# 2024-8-17-.net
KiCad netlist of a schematic drawn in EasyEDA Pro
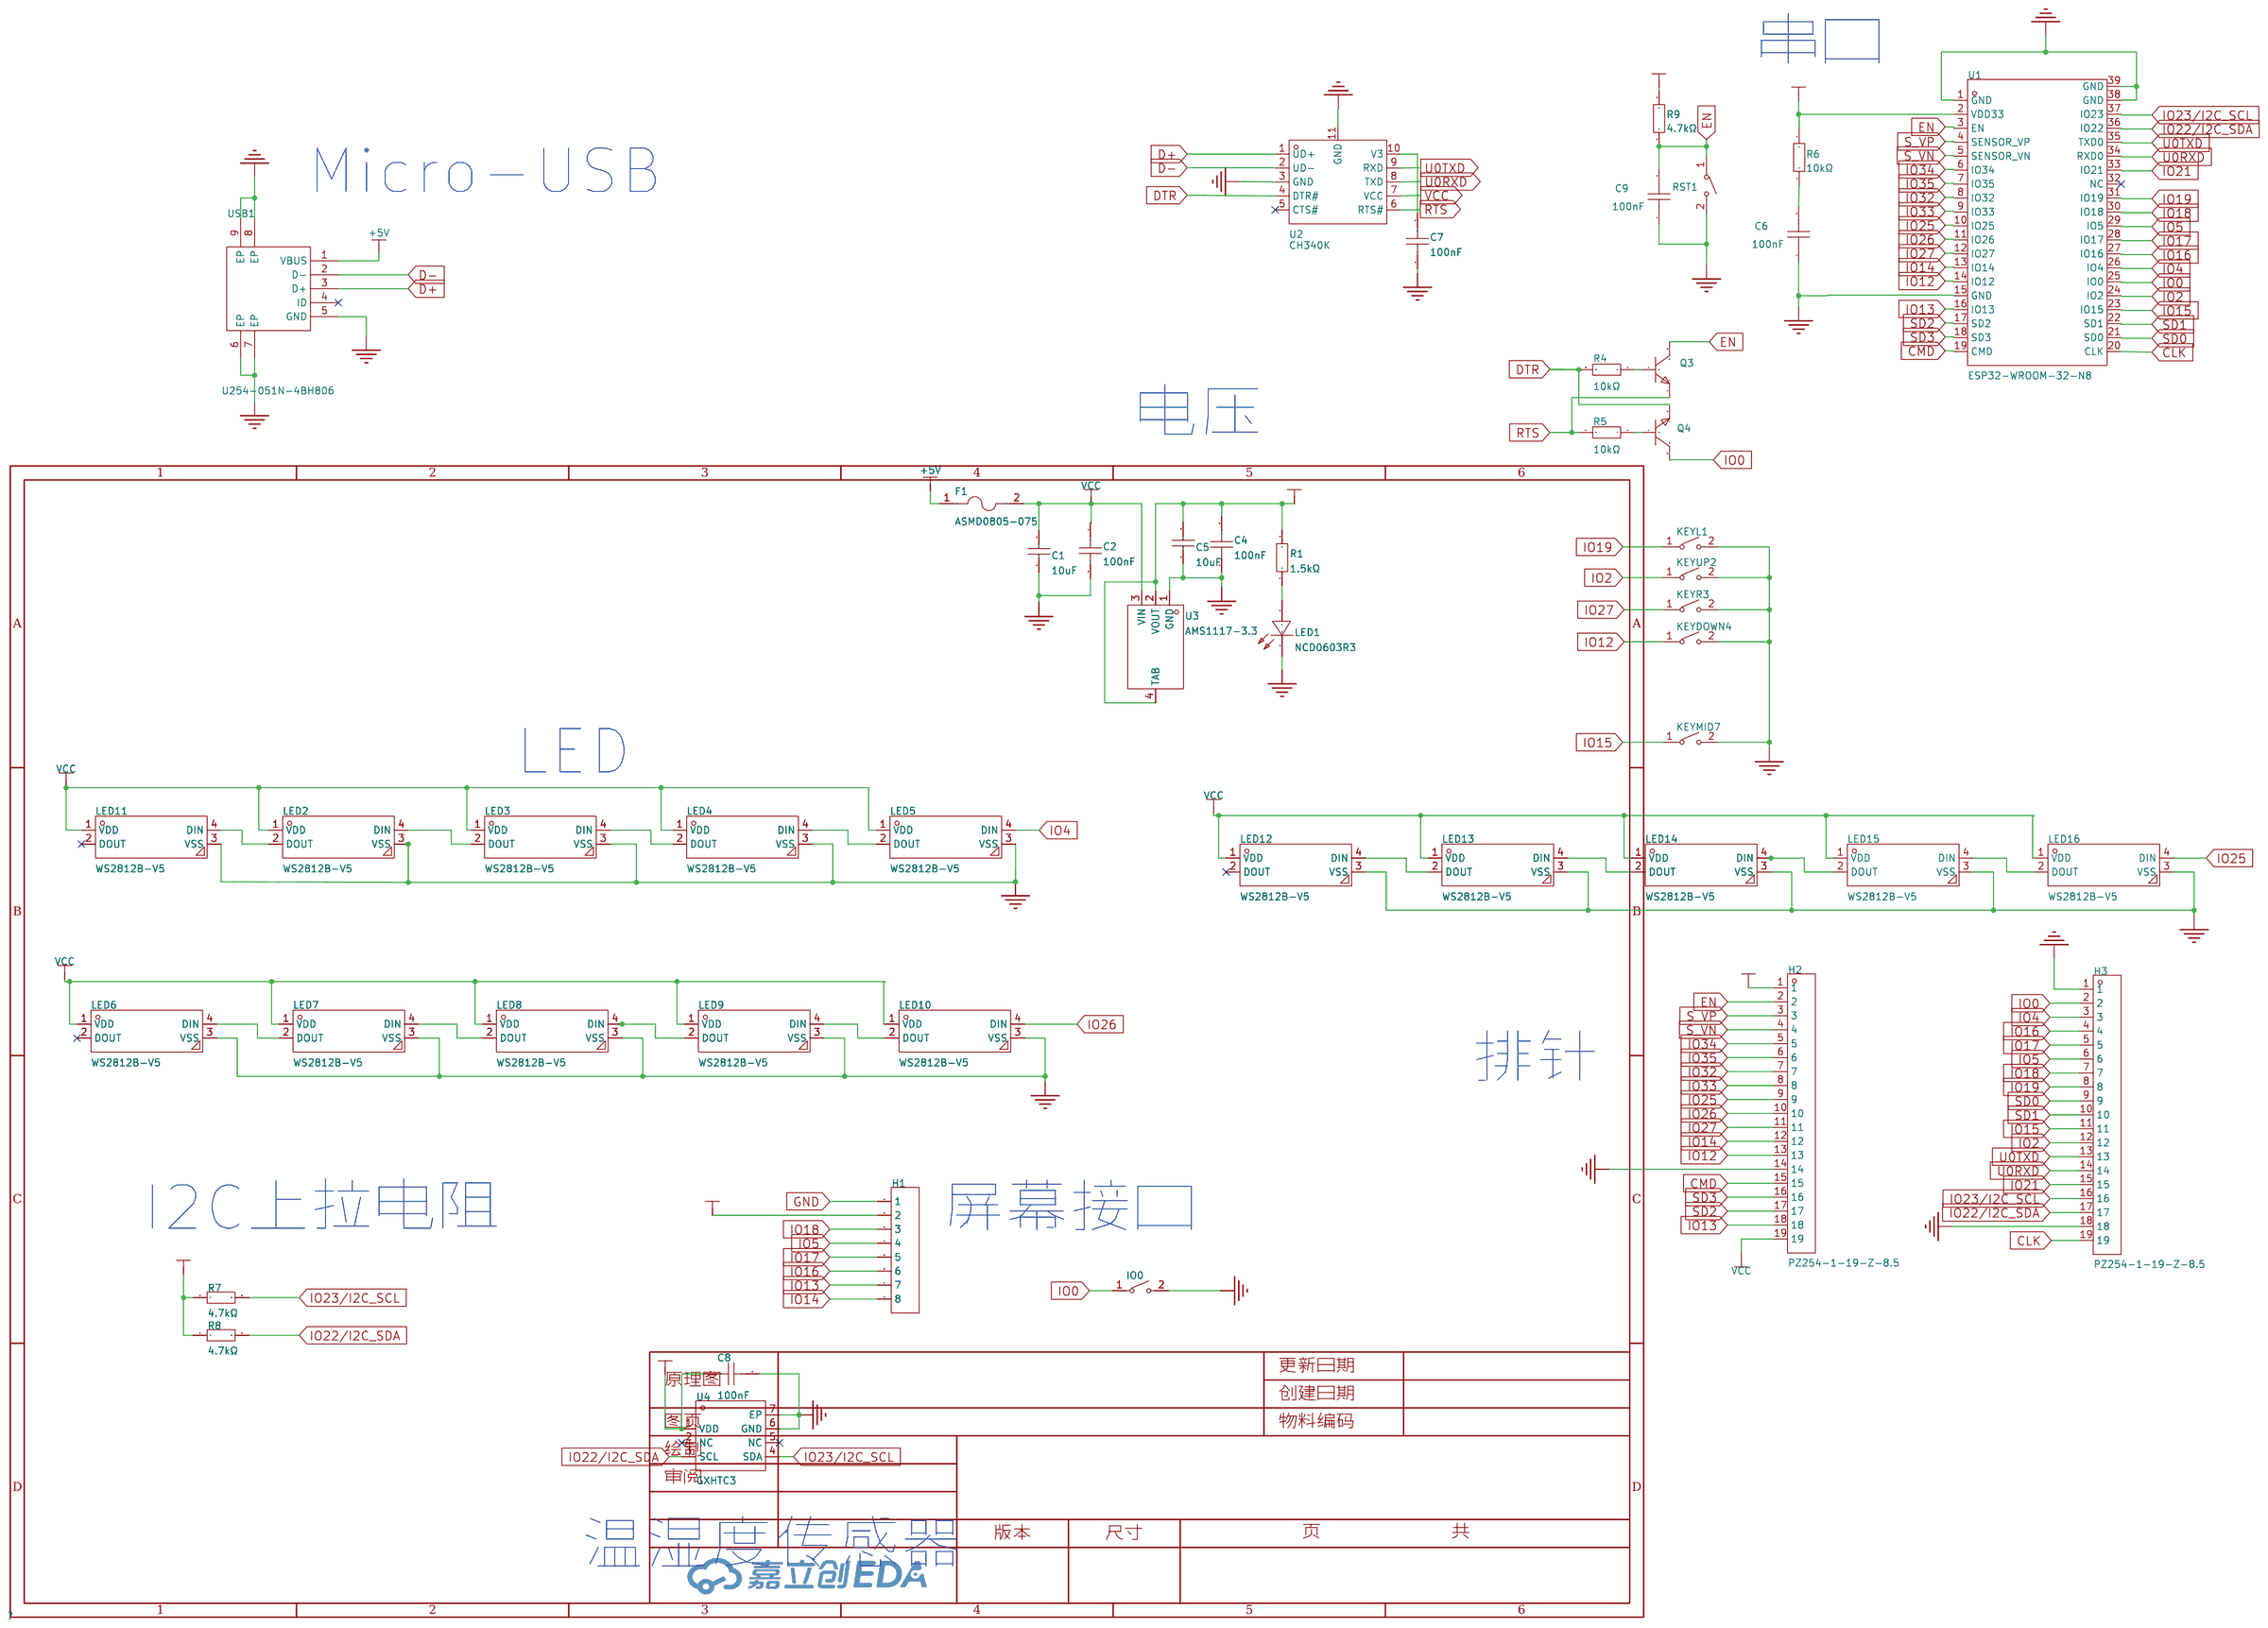
[diagram p0: schematic sheet]

(export (version "E")
  (design (tool "Eeschema 10.0.6"))
  (components
    (comp (ref "C1")
      (value "10uF")
      (footprint "easyedapro:C0805")
      (description "容值:10uF;精度:±10%;额定电压:16V;材质(温度系数):X5R;")
      (fields
        (field (name "Manufacturer Part") "CL21A106KOQNNNE")
        (field (name "Manufacturer") "SAMSUNG(三星)")
      )
      (libsource (lib "easyedapro") (part "CL21A106KOQNNNE"))
    )
    (comp (ref "C2")
      (value "100nF")
      (footprint "easyedapro:C0603")
      (description "容值:100nF;精度:±10%;额定电压:50V;材质(温度系数):X7R;")
      (fields
        (field (name "Manufacturer Part") "CC0603KRX7R9BB104")
        (field (name "Manufacturer") "YAGEO(国巨)")
      )
      (libsource (lib "easyedapro") (part "CC0603KRX7R9BB104"))
    )
    (comp (ref "C4")
      (value "100nF")
      (footprint "easyedapro:C0603")
      (description "容值:100nF;精度:±10%;额定电压:50V;材质(温度系数):X7R;")
      (fields
        (field (name "Manufacturer Part") "CC0603KRX7R9BB104")
        (field (name "Manufacturer") "YAGEO(国巨)")
      )
      (libsource (lib "easyedapro") (part "CC0603KRX7R9BB104"))
    )
    (comp (ref "C5")
      (value "10uF")
      (footprint "easyedapro:C0805")
      (description "容值:10uF;精度:±10%;额定电压:16V;材质(温度系数):X5R;")
      (fields
        (field (name "Manufacturer Part") "CL21A106KOQNNNE")
        (field (name "Manufacturer") "SAMSUNG(三星)")
      )
      (libsource (lib "easyedapro") (part "CL21A106KOQNNNE"))
    )
    (comp (ref "C6")
      (value "100nF")
      (footprint "easyedapro:C0603")
      (description "容值:100nF;精度:±10%;额定电压:50V;材质(温度系数):X7R;")
      (fields
        (field (name "Manufacturer Part") "CC0603KRX7R9BB104")
        (field (name "Manufacturer") "YAGEO(国巨)")
      )
      (libsource (lib "easyedapro") (part "CC0603KRX7R9BB104"))
    )
    (comp (ref "C7")
      (value "100nF")
      (footprint "easyedapro:C0603")
      (description "容值:100nF;精度:±10%;额定电压:50V;材质(温度系数):X7R;")
      (fields
        (field (name "Manufacturer Part") "CC0603KRX7R9BB104")
        (field (name "Manufacturer") "YAGEO(国巨)")
      )
      (libsource (lib "easyedapro") (part "CC0603KRX7R9BB104"))
    )
    (comp (ref "C8")
      (value "100nF")
      (footprint "easyedapro:C0603")
      (description "容值:100nF;精度:±10%;额定电压:50V;材质(温度系数):X7R;")
      (fields
        (field (name "Manufacturer Part") "CC0603KRX7R9BB104")
        (field (name "Manufacturer") "YAGEO(国巨)")
      )
      (libsource (lib "easyedapro") (part "CC0603KRX7R9BB104"))
    )
    (comp (ref "C9")
      (value "100nF")
      (footprint "easyedapro:C0603")
      (description "容值:100nF;精度:±10%;额定电压:50V;材质(温度系数):X7R;")
      (fields
        (field (name "Manufacturer Part") "CC0603KRX7R9BB104")
        (field (name "Manufacturer") "YAGEO(国巨)")
      )
      (libsource (lib "easyedapro") (part "CC0603KRX7R9BB104"))
    )
    (comp (ref "F1")
      (value "ASMD0805-075")
      (footprint "easyedapro:F0805")
      (description "最大电压:6V;最大电流:40A;保持电流:750mA;跳闸电流:1.5A;")
      (fields (field (name "Manufacturer") "JDTfuse(集电通)"))
      (libsource (lib "easyedapro") (part "ASMD0805-075"))
    )
    (comp (ref "H1")
      (value "~")
      (footprint "easyedapro:HDR-TH_8P-P2.54-V-F-1")
      (libsource (lib "easyedapro") (part "Header-Female-2.54_1x8"))
    )
    (comp (ref "H2")
      (value "PZ254-1-19-Z-8.5")
      (footprint "easyedapro:HDR-TH_19P-P2.54-V-M")
      (fields (field (name "Manufacturer") "HCTL(华灿天禄)"))
      (libsource (lib "easyedapro") (part "PZ254-1-19-Z-8.5"))
    )
    (comp (ref "H3")
      (value "PZ254-1-19-Z-8.5")
      (footprint "easyedapro:HDR-TH_19P-P2.54-V-M")
      (fields (field (name "Manufacturer") "HCTL(华灿天禄)"))
      (libsource (lib "easyedapro") (part "PZ254-1-19-Z-8.5"))
    )
    (comp (ref "IO0")
      (value "TS-1088R-02526")
      (footprint "easyedapro:SW-SMD_L3.9-W3.0-P4.45")
      (description "电路结构:单刀单掷;按钮形状:圆形按钮;安装方式:立贴;开关长度:3.9mm;开关宽度:2.93mm;开关高度:2.5mm;触点电流:50mA;额定电压(DC):12V;带灯:-;机械寿命:-;")
      (fields (field (name "Manufacturer") "XUNPU(讯普)"))
      (libsource (lib "easyedapro") (part "TS-1088R-02526"))
    )
    (comp (ref "KEYDOWN4")
      (value "TS-1088R-02526")
      (footprint "easyedapro:SW-SMD_L3.9-W3.0-P4.45")
      (description "电路结构:单刀单掷;按钮形状:圆形按钮;安装方式:立贴;开关长度:3.9mm;开关宽度:2.93mm;开关高度:2.5mm;触点电流:50mA;额定电压(DC):12V;带灯:-;机械寿命:-;")
      (fields (field (name "Manufacturer") "XUNPU(讯普)"))
      (libsource (lib "easyedapro") (part "TS-1088R-02526"))
    )
    (comp (ref "KEYL1")
      (value "TS-1088R-02526")
      (footprint "easyedapro:SW-SMD_L3.9-W3.0-P4.45")
      (description "电路结构:单刀单掷;按钮形状:圆形按钮;安装方式:立贴;开关长度:3.9mm;开关宽度:2.93mm;开关高度:2.5mm;触点电流:50mA;额定电压(DC):12V;带灯:-;机械寿命:-;")
      (fields (field (name "Manufacturer") "XUNPU(讯普)"))
      (libsource (lib "easyedapro") (part "TS-1088R-02526"))
    )
    (comp (ref "KEYMID7")
      (value "TS-1088R-02526")
      (footprint "easyedapro:SW-SMD_L3.9-W3.0-P4.45")
      (description "电路结构:单刀单掷;按钮形状:圆形按钮;安装方式:立贴;开关长度:3.9mm;开关宽度:2.93mm;开关高度:2.5mm;触点电流:50mA;额定电压(DC):12V;带灯:-;机械寿命:-;")
      (fields (field (name "Manufacturer") "XUNPU(讯普)"))
      (libsource (lib "easyedapro") (part "TS-1088R-02526"))
    )
    (comp (ref "KEYR3")
      (value "TS-1088R-02526")
      (footprint "easyedapro:SW-SMD_L3.9-W3.0-P4.45")
      (description "电路结构:单刀单掷;按钮形状:圆形按钮;安装方式:立贴;开关长度:3.9mm;开关宽度:2.93mm;开关高度:2.5mm;触点电流:50mA;额定电压(DC):12V;带灯:-;机械寿命:-;")
      (fields (field (name "Manufacturer") "XUNPU(讯普)"))
      (libsource (lib "easyedapro") (part "TS-1088R-02526"))
    )
    (comp (ref "KEYUP2")
      (value "TS-1088R-02526")
      (footprint "easyedapro:SW-SMD_L3.9-W3.0-P4.45")
      (description "电路结构:单刀单掷;按钮形状:圆形按钮;安装方式:立贴;开关长度:3.9mm;开关宽度:2.93mm;开关高度:2.5mm;触点电流:50mA;额定电压(DC):12V;带灯:-;机械寿命:-;")
      (fields (field (name "Manufacturer") "XUNPU(讯普)"))
      (libsource (lib "easyedapro") (part "TS-1088R-02526"))
    )
    (comp (ref "LED1")
      (value "NCD0603R3")
      (footprint "easyedapro:LED0603-R-RD_RED")
      (fields (field (name "Manufacturer") "国星光电"))
      (libsource (lib "easyedapro") (part "NCD0603R3"))
    )
    (comp (ref "LED2")
      (value "WS2812B-V5")
      (footprint "easyedapro:LED-SMD_4P-L5.0-W5.0-LS5.4-TL-1")
      (description "（注意防潮，请查阅规格书中对应具体内容）")
      (fields (field (name "Manufacturer") "worldsemi"))
      (libsource (lib "easyedapro") (part "WS2812B-V5_C2846931"))
    )
    (comp (ref "LED3")
      (value "WS2812B-V5")
      (footprint "easyedapro:LED-SMD_4P-L5.0-W5.0-LS5.4-TL-1")
      (description "（注意防潮，请查阅规格书中对应具体内容）")
      (fields (field (name "Manufacturer") "worldsemi"))
      (libsource (lib "easyedapro") (part "WS2812B-V5_C2846931"))
    )
    (comp (ref "LED4")
      (value "WS2812B-V5")
      (footprint "easyedapro:LED-SMD_4P-L5.0-W5.0-LS5.4-TL-1")
      (description "（注意防潮，请查阅规格书中对应具体内容）")
      (fields (field (name "Manufacturer") "worldsemi"))
      (libsource (lib "easyedapro") (part "WS2812B-V5_C2846931"))
    )
    (comp (ref "LED5")
      (value "WS2812B-V5")
      (footprint "easyedapro:LED-SMD_4P-L5.0-W5.0-LS5.4-TL-1")
      (description "（注意防潮，请查阅规格书中对应具体内容）")
      (fields (field (name "Manufacturer") "worldsemi"))
      (libsource (lib "easyedapro") (part "WS2812B-V5_C2846931"))
    )
    (comp (ref "LED6")
      (value "WS2812B-V5")
      (footprint "easyedapro:LED-SMD_4P-L5.0-W5.0-LS5.4-TL-1")
      (description "（注意防潮，请查阅规格书中对应具体内容）")
      (fields (field (name "Manufacturer") "worldsemi"))
      (libsource (lib "easyedapro") (part "WS2812B-V5_C2846931"))
    )
    (comp (ref "LED7")
      (value "WS2812B-V5")
      (footprint "easyedapro:LED-SMD_4P-L5.0-W5.0-LS5.4-TL-1")
      (description "（注意防潮，请查阅规格书中对应具体内容）")
      (fields (field (name "Manufacturer") "worldsemi"))
      (libsource (lib "easyedapro") (part "WS2812B-V5_C2846931"))
    )
    (comp (ref "LED8")
      (value "WS2812B-V5")
      (footprint "easyedapro:LED-SMD_4P-L5.0-W5.0-LS5.4-TL-1")
      (description "（注意防潮，请查阅规格书中对应具体内容）")
      (fields (field (name "Manufacturer") "worldsemi"))
      (libsource (lib "easyedapro") (part "WS2812B-V5_C2846931"))
    )
    (comp (ref "LED9")
      (value "WS2812B-V5")
      (footprint "easyedapro:LED-SMD_4P-L5.0-W5.0-LS5.4-TL-1")
      (description "（注意防潮，请查阅规格书中对应具体内容）")
      (fields (field (name "Manufacturer") "worldsemi"))
      (libsource (lib "easyedapro") (part "WS2812B-V5_C2846931"))
    )
    (comp (ref "LED10")
      (value "WS2812B-V5")
      (footprint "easyedapro:LED-SMD_4P-L5.0-W5.0-LS5.4-TL-1")
      (description "（注意防潮，请查阅规格书中对应具体内容）")
      (fields (field (name "Manufacturer") "worldsemi"))
      (libsource (lib "easyedapro") (part "WS2812B-V5_C2846931"))
    )
    (comp (ref "LED11")
      (value "WS2812B-V5")
      (footprint "easyedapro:LED-SMD_4P-L5.0-W5.0-LS5.4-TL-1")
      (description "（注意防潮，请查阅规格书中对应具体内容）")
      (fields (field (name "Manufacturer") "worldsemi"))
      (libsource (lib "easyedapro") (part "WS2812B-V5_C2846931"))
    )
    (comp (ref "LED12")
      (value "WS2812B-V5")
      (footprint "easyedapro:LED-SMD_4P-L5.0-W5.0-LS5.4-TL-1")
      (description "（注意防潮，请查阅规格书中对应具体内容）")
      (fields (field (name "Manufacturer") "worldsemi"))
      (libsource (lib "easyedapro") (part "WS2812B-V5_C2846931"))
    )
    (comp (ref "LED13")
      (value "WS2812B-V5")
      (footprint "easyedapro:LED-SMD_4P-L5.0-W5.0-LS5.4-TL-1")
      (description "（注意防潮，请查阅规格书中对应具体内容）")
      (fields (field (name "Manufacturer") "worldsemi"))
      (libsource (lib "easyedapro") (part "WS2812B-V5_C2846931"))
    )
    (comp (ref "LED14")
      (value "WS2812B-V5")
      (footprint "easyedapro:LED-SMD_4P-L5.0-W5.0-LS5.4-TL-1")
      (description "（注意防潮，请查阅规格书中对应具体内容）")
      (fields (field (name "Manufacturer") "worldsemi"))
      (libsource (lib "easyedapro") (part "WS2812B-V5_C2846931"))
    )
    (comp (ref "LED15")
      (value "WS2812B-V5")
      (footprint "easyedapro:LED-SMD_4P-L5.0-W5.0-LS5.4-TL-1")
      (description "（注意防潮，请查阅规格书中对应具体内容）")
      (fields (field (name "Manufacturer") "worldsemi"))
      (libsource (lib "easyedapro") (part "WS2812B-V5_C2846931"))
    )
    (comp (ref "LED16")
      (value "WS2812B-V5")
      (footprint "easyedapro:LED-SMD_4P-L5.0-W5.0-LS5.4-TL-1")
      (description "（注意防潮，请查阅规格书中对应具体内容）")
      (fields (field (name "Manufacturer") "worldsemi"))
      (libsource (lib "easyedapro") (part "WS2812B-V5_C2846931"))
    )
    (comp (ref "Q3")
      (value "L8050QLT1G")
      (footprint "easyedapro:SOT-23-3_L2.9-W1.3-P1.90-LS2.4-BR")
      (description "晶体管类型:NPN;集电极电流(Ic):800mA;集射极击穿电压(Vceo):25V;功率(Pd):225mW;")
      (fields (field (name "Manufacturer") "LRC(乐山无线电)"))
      (libsource (lib "easyedapro") (part "L8050QLT1G"))
    )
    (comp (ref "Q4")
      (value "L8050QLT1G")
      (footprint "easyedapro:SOT-23-3_L2.9-W1.3-P1.90-LS2.4-BR")
      (description "晶体管类型:NPN;集电极电流(Ic):800mA;集射极击穿电压(Vceo):25V;功率(Pd):225mW;")
      (fields (field (name "Manufacturer") "LRC(乐山无线电)"))
      (libsource (lib "easyedapro") (part "L8050QLT1G"))
    )
    (comp (ref "R1")
      (value "1.5kΩ")
      (footprint "easyedapro:R0805")
      (description "电阻类型:厚膜电阻;阻值:1.5kΩ;精度:±1%;功率:125mW;最大工作电压:150V;温度系数:±100ppm/°C;")
      (fields
        (field (name "Manufacturer Part") "0805W8F1501T5E")
        (field (name "Manufacturer") "UNI-ROYAL(厚声)")
      )
      (libsource (lib "easyedapro") (part "0805W8F1501T5E"))
    )
    (comp (ref "R4")
      (value "10kΩ")
      (footprint "easyedapro:R0603")
      (description "电阻类型:薄膜电阻;阻值:10kΩ;精度:±0.1%;功率:100mW;温度系数:±25ppm/;最大工作电压:75V;工作温度范围:-55~+155;")
      (fields
        (field (name "Manufacturer Part") "TR0603B10K0P0525Z")
        (field (name "Manufacturer") "EVER OHMS(天二科技)")
      )
      (libsource (lib "easyedapro") (part "TR0603B10KP05250.1W"))
    )
    (comp (ref "R5")
      (value "10kΩ")
      (footprint "easyedapro:R0603")
      (description "电阻类型:薄膜电阻;阻值:10kΩ;精度:±0.1%;功率:100mW;温度系数:±25ppm/;最大工作电压:75V;工作温度范围:-55~+155;")
      (fields
        (field (name "Manufacturer Part") "TR0603B10K0P0525Z")
        (field (name "Manufacturer") "EVER OHMS(天二科技)")
      )
      (libsource (lib "easyedapro") (part "TR0603B10KP05250.1W"))
    )
    (comp (ref "R6")
      (value "10kΩ")
      (footprint "easyedapro:R0603")
      (description "电阻类型:薄膜电阻;阻值:10kΩ;精度:±0.1%;功率:100mW;温度系数:±25ppm/;最大工作电压:75V;工作温度范围:-55~+155;")
      (fields
        (field (name "Manufacturer Part") "TR0603B10K0P0525Z")
        (field (name "Manufacturer") "EVER OHMS(天二科技)")
      )
      (libsource (lib "easyedapro") (part "TR0603B10KP05250.1W"))
    )
    (comp (ref "R7")
      (value "4.7kΩ")
      (footprint "easyedapro:R0805")
      (description "电阻类型:厚膜电阻;阻值:4.7kΩ;精度:±1%;功率:125mW;最大工作电压:150V;温度系数:±100ppm/°C;")
      (fields
        (field (name "Manufacturer Part") "0805W8F4701T5E")
        (field (name "Manufacturer") "UNI-ROYAL(厚声)")
      )
      (libsource (lib "easyedapro") (part "0805W8F4701T5E"))
    )
    (comp (ref "R8")
      (value "4.7kΩ")
      (footprint "easyedapro:R0805")
      (description "电阻类型:厚膜电阻;阻值:4.7kΩ;精度:±1%;功率:125mW;最大工作电压:150V;温度系数:±100ppm/°C;")
      (fields
        (field (name "Manufacturer Part") "0805W8F4701T5E")
        (field (name "Manufacturer") "UNI-ROYAL(厚声)")
      )
      (libsource (lib "easyedapro") (part "0805W8F4701T5E"))
    )
    (comp (ref "R9")
      (value "4.7kΩ")
      (footprint "easyedapro:R0805")
      (description "电阻类型:厚膜电阻;阻值:4.7kΩ;精度:±1%;功率:125mW;最大工作电压:150V;温度系数:±100ppm/°C;")
      (fields
        (field (name "Manufacturer Part") "0805W8F4701T5E")
        (field (name "Manufacturer") "UNI-ROYAL(厚声)")
      )
      (libsource (lib "easyedapro") (part "0805W8F4701T5E"))
    )
    (comp (ref "RST1")
      (value "TS-1088R-02526")
      (footprint "easyedapro:SW-SMD_L3.9-W3.0-P4.45")
      (description "电路结构:单刀单掷;按钮形状:圆形按钮;安装方式:立贴;开关长度:3.9mm;开关宽度:2.93mm;开关高度:2.5mm;触点电流:50mA;额定电压(DC):12V;带灯:-;机械寿命:-;")
      (fields (field (name "Manufacturer") "XUNPU(讯普)"))
      (libsource (lib "easyedapro") (part "TS-1088R-02526"))
    )
    (comp (ref "U1")
      (value "ESP32-WROOM-32-N8")
      (footprint "easyedapro:WIFIM-SMD_39P-L25.5-W18.0-P1.27")
      (fields (field (name "Manufacturer") "ESPRESSIF(乐鑫)"))
      (libsource (lib "easyedapro") (part "ESP32-WROOM-32(8MB)"))
    )
    (comp (ref "U2")
      (value "CH340K")
      (footprint "easyedapro:ESOP-10_L4.9-W3.9-P1.00-LS6.0-BL-EP")
      (fields (field (name "Manufacturer") "WCH(南京沁恒)"))
      (libsource (lib "easyedapro") (part "CH340K_C18208922"))
    )
    (comp (ref "U3")
      (value "AMS1117-3.3")
      (footprint "easyedapro:SOT-223-3_L6.5-W3.4-P2.30-LS7.0-BR")
      (description "输出类型:固定;最大输入电压:18V;输出电压:3.3V;最大输出电流:800mA;电源纹波抑制比(PSRR):-;输出极性:正极;")
      (fields (field (name "Manufacturer") "PUOLOP(迪浦)"))
      (libsource (lib "easyedapro") (part "AMS1117-3.3_C351784"))
    )
    (comp (ref "U4")
      (value "GXHTC3")
      (footprint "easyedapro:DFN-6_L2.0-W2.0-P0.50-BL-EP")
      (fields (field (name "Manufacturer") "GXCAS(中科银河芯)"))
      (libsource (lib "easyedapro") (part "GXHTC3"))
    )
    (comp (ref "USB1")
      (value "U254-051N-4BH806")
      (footprint "easyedapro:MICRO-USB-SMD_U254-051N-4BH806")
      (fields (field (name "Manufacturer") "XKB Connectivity(中国星坤)"))
      (libsource (lib "easyedapro") (part "U254-051N-4BH806"))
    )
  )
  (nets
    (net (code "1") (name "+5V") (class "Default")
      (node (ref "F1") (pin "1") (pinfunction "1_1") (pintype "unspecified"))
      (node (ref "USB1") (pin "1") (pinfunction "VBUS_1") (pintype "unspecified"))
    )
    (net (code "2") (name "3V3") (class "Default")
      (node (ref "C4") (pin "2") (pinfunction "2_2") (pintype "unspecified"))
      (node (ref "C5") (pin "2") (pinfunction "2_2") (pintype "input"))
      (node (ref "C8") (pin "2") (pinfunction "2_2") (pintype "unspecified"))
      (node (ref "H1") (pin "2") (pinfunction "2_2") (pintype "input"))
      (node (ref "H2") (pin "1") (pinfunction "1_1") (pintype "unspecified"))
      (node (ref "R1") (pin "2") (pinfunction "2_2") (pintype "input"))
      (node (ref "R6") (pin "1") (pinfunction "1_1") (pintype "input"))
      (node (ref "R7") (pin "1") (pinfunction "1_1") (pintype "input"))
      (node (ref "R8") (pin "1") (pinfunction "1_1") (pintype "input"))
      (node (ref "R9") (pin "2") (pinfunction "2_2") (pintype "input"))
      (node (ref "U1") (pin "2") (pinfunction "VDD33_2") (pintype "unspecified"))
      (node (ref "U3") (pin "2") (pinfunction "VOUT_2") (pintype "unspecified"))
      (node (ref "U3") (pin "4") (pinfunction "TAB_4") (pintype "unspecified"))
      (node (ref "U4") (pin "1") (pinfunction "VDD_1") (pintype "unspecified"))
    )
    (net (code "3") (name "CLK") (class "Default")
      (node (ref "H3") (pin "19") (pinfunction "19_19") (pintype "unspecified"))
      (node (ref "U1") (pin "20") (pinfunction "CLK_20") (pintype "unspecified"))
    )
    (net (code "4") (name "CMD") (class "Default")
      (node (ref "H2") (pin "15") (pinfunction "15_15") (pintype "unspecified"))
      (node (ref "U1") (pin "19") (pinfunction "CMD_19") (pintype "unspecified"))
    )
    (net (code "5") (name "D+") (class "Default")
      (node (ref "U2") (pin "1") (pinfunction "UD+_1") (pintype "unspecified"))
      (node (ref "USB1") (pin "3") (pinfunction "D+_3") (pintype "unspecified"))
    )
    (net (code "6") (name "D-") (class "Default")
      (node (ref "USB1") (pin "2") (pinfunction "D-_2") (pintype "unspecified"))
    )
    (net (code "7") (name "DTR") (class "Default")
      (node (ref "Q4") (pin "2") (pinfunction "E_2") (pintype "unspecified"))
      (node (ref "R4") (pin "2") (pinfunction "2_2") (pintype "input"))
      (node (ref "U2") (pin "4") (pinfunction "DTR#_4") (pintype "unspecified"))
    )
    (net (code "8") (name "EN") (class "Default")
      (node (ref "C9") (pin "2") (pinfunction "2_2") (pintype "unspecified"))
      (node (ref "H2") (pin "2") (pinfunction "2_2") (pintype "unspecified"))
      (node (ref "Q3") (pin "3") (pinfunction "C_3") (pintype "unspecified"))
      (node (ref "R9") (pin "1") (pinfunction "1_1") (pintype "input"))
      (node (ref "RST1") (pin "1") (pinfunction "1_1") (pintype "unspecified"))
      (node (ref "U1") (pin "3") (pinfunction "EN_3") (pintype "unspecified"))
    )
    (net (code "9") (name "GND") (class "Default")
      (node (ref "C1") (pin "1") (pinfunction "1_1") (pintype "input"))
      (node (ref "C2") (pin "1") (pinfunction "1_1") (pintype "unspecified"))
      (node (ref "C4") (pin "1") (pinfunction "1_1") (pintype "unspecified"))
      (node (ref "C5") (pin "1") (pinfunction "1_1") (pintype "input"))
      (node (ref "C6") (pin "1") (pinfunction "1_1") (pintype "unspecified"))
      (node (ref "C7") (pin "1") (pinfunction "1_1") (pintype "unspecified"))
      (node (ref "C8") (pin "1") (pinfunction "1_1") (pintype "unspecified"))
      (node (ref "C9") (pin "1") (pinfunction "1_1") (pintype "unspecified"))
      (node (ref "H1") (pin "1") (pinfunction "1_1") (pintype "input"))
      (node (ref "H2") (pin "14") (pinfunction "14_14") (pintype "unspecified"))
      (node (ref "H3") (pin "1") (pinfunction "1_1") (pintype "unspecified"))
      (node (ref "H3") (pin "18") (pinfunction "18_18") (pintype "unspecified"))
      (node (ref "IO0") (pin "2") (pinfunction "2_2") (pintype "unspecified"))
      (node (ref "KEYDOWN4") (pin "2") (pinfunction "2_2") (pintype "unspecified"))
      (node (ref "KEYL1") (pin "2") (pinfunction "2_2") (pintype "unspecified"))
      (node (ref "KEYMID7") (pin "2") (pinfunction "2_2") (pintype "unspecified"))
      (node (ref "KEYR3") (pin "2") (pinfunction "2_2") (pintype "unspecified"))
      (node (ref "KEYUP2") (pin "2") (pinfunction "2_2") (pintype "unspecified"))
      (node (ref "LED1") (pin "2") (pinfunction "K_2") (pintype "unspecified"))
      (node (ref "LED10") (pin "3") (pinfunction "VSS_3") (pintype "unspecified"))
      (node (ref "LED11") (pin "3") (pinfunction "VSS_3") (pintype "unspecified"))
      (node (ref "LED12") (pin "3") (pinfunction "VSS_3") (pintype "unspecified"))
      (node (ref "LED13") (pin "3") (pinfunction "VSS_3") (pintype "unspecified"))
      (node (ref "LED14") (pin "3") (pinfunction "VSS_3") (pintype "unspecified"))
      (node (ref "LED15") (pin "3") (pinfunction "VSS_3") (pintype "unspecified"))
      (node (ref "LED16") (pin "3") (pinfunction "VSS_3") (pintype "unspecified"))
      (node (ref "LED2") (pin "3") (pinfunction "VSS_3") (pintype "unspecified"))
      (node (ref "LED3") (pin "3") (pinfunction "VSS_3") (pintype "unspecified"))
      (node (ref "LED4") (pin "3") (pinfunction "VSS_3") (pintype "unspecified"))
      (node (ref "LED5") (pin "3") (pinfunction "VSS_3") (pintype "unspecified"))
      (node (ref "LED6") (pin "3") (pinfunction "VSS_3") (pintype "unspecified"))
      (node (ref "LED7") (pin "3") (pinfunction "VSS_3") (pintype "unspecified"))
      (node (ref "LED8") (pin "3") (pinfunction "VSS_3") (pintype "unspecified"))
      (node (ref "LED9") (pin "3") (pinfunction "VSS_3") (pintype "unspecified"))
      (node (ref "RST1") (pin "2") (pinfunction "2_2") (pintype "unspecified"))
      (node (ref "U1") (pin "15") (pinfunction "GND_15") (pintype "unspecified"))
      (node (ref "U1") (pin "39") (pinfunction "GND_39") (pintype "unspecified"))
      (node (ref "U2") (pin "11") (pinfunction "GND_11") (pintype "unspecified"))
      (node (ref "U2") (pin "3") (pinfunction "GND_3") (pintype "unspecified"))
      (node (ref "U3") (pin "1") (pinfunction "GND_1") (pintype "unspecified"))
      (node (ref "U4") (pin "6") (pinfunction "GND_6") (pintype "unspecified"))
      (node (ref "U4") (pin "7") (pinfunction "EP_7") (pintype "unspecified"))
      (node (ref "USB1") (pin "5") (pinfunction "GND_5") (pintype "unspecified"))
      (node (ref "USB1") (pin "6") (pinfunction "EP_6") (pintype "unspecified"))
      (node (ref "USB1") (pin "7") (pinfunction "EP_7") (pintype "unspecified"))
      (node (ref "USB1") (pin "8") (pinfunction "EP_8") (pintype "unspecified"))
      (node (ref "USB1") (pin "9") (pinfunction "EP_9") (pintype "unspecified"))
    )
    (net (code "10") (name "IO0") (class "Default")
      (node (ref "H3") (pin "2") (pinfunction "2_2") (pintype "unspecified"))
      (node (ref "IO0") (pin "1") (pinfunction "1_1") (pintype "unspecified"))
      (node (ref "Q4") (pin "3") (pinfunction "C_3") (pintype "unspecified"))
    )
    (net (code "11") (name "IO2") (class "Default")
      (node (ref "H3") (pin "12") (pinfunction "12_12") (pintype "unspecified"))
      (node (ref "KEYUP2") (pin "1") (pinfunction "1_1") (pintype "unspecified"))
    )
    (net (code "12") (name "IO4") (class "Default")
      (node (ref "H3") (pin "3") (pinfunction "3_3") (pintype "unspecified"))
      (node (ref "LED5") (pin "4") (pinfunction "DIN_4") (pintype "unspecified"))
    )
    (net (code "13") (name "IO5") (class "Default")
      (node (ref "H1") (pin "4") (pinfunction "4_4") (pintype "input"))
      (node (ref "H3") (pin "6") (pinfunction "6_6") (pintype "unspecified"))
    )
    (net (code "14") (name "IO12") (class "Default")
      (node (ref "H2") (pin "13") (pinfunction "13_13") (pintype "unspecified"))
      (node (ref "KEYDOWN4") (pin "1") (pinfunction "1_1") (pintype "unspecified"))
      (node (ref "U1") (pin "14") (pinfunction "IO12_14") (pintype "unspecified"))
    )
    (net (code "15") (name "IO13") (class "Default")
      (node (ref "H1") (pin "7") (pinfunction "7_7") (pintype "input"))
      (node (ref "H2") (pin "18") (pinfunction "18_18") (pintype "unspecified"))
      (node (ref "U1") (pin "16") (pinfunction "IO13_16") (pintype "unspecified"))
    )
    (net (code "16") (name "IO14") (class "Default")
      (node (ref "H1") (pin "8") (pinfunction "8_8") (pintype "input"))
      (node (ref "H2") (pin "12") (pinfunction "12_12") (pintype "unspecified"))
      (node (ref "U1") (pin "13") (pinfunction "IO14_13") (pintype "unspecified"))
    )
    (net (code "17") (name "IO15") (class "Default")
      (node (ref "H3") (pin "11") (pinfunction "11_11") (pintype "unspecified"))
      (node (ref "KEYMID7") (pin "1") (pinfunction "1_1") (pintype "unspecified"))
    )
    (net (code "18") (name "IO16") (class "Default")
      (node (ref "H1") (pin "6") (pinfunction "6_6") (pintype "input"))
      (node (ref "H3") (pin "4") (pinfunction "4_4") (pintype "unspecified"))
    )
    (net (code "19") (name "IO17") (class "Default")
      (node (ref "H1") (pin "5") (pinfunction "5_5") (pintype "input"))
      (node (ref "H3") (pin "5") (pinfunction "5_5") (pintype "unspecified"))
    )
    (net (code "20") (name "IO18") (class "Default")
      (node (ref "H1") (pin "3") (pinfunction "3_3") (pintype "input"))
      (node (ref "H3") (pin "7") (pinfunction "7_7") (pintype "unspecified"))
    )
    (net (code "21") (name "IO19") (class "Default")
      (node (ref "H3") (pin "8") (pinfunction "8_8") (pintype "unspecified"))
      (node (ref "KEYL1") (pin "1") (pinfunction "1_1") (pintype "unspecified"))
    )
    (net (code "22") (name "IO21") (class "Default")
      (node (ref "H3") (pin "15") (pinfunction "15_15") (pintype "unspecified"))
    )
    (net (code "23") (name "IO22{slash}I2C_SDA") (class "Default")
      (node (ref "H3") (pin "17") (pinfunction "17_17") (pintype "unspecified"))
      (node (ref "R8") (pin "2") (pinfunction "2_2") (pintype "input"))
      (node (ref "U4") (pin "3") (pinfunction "SCL_3") (pintype "unspecified"))
    )
    (net (code "24") (name "IO23{slash}I2C_SCL") (class "Default")
      (node (ref "H3") (pin "16") (pinfunction "16_16") (pintype "unspecified"))
      (node (ref "R7") (pin "2") (pinfunction "2_2") (pintype "input"))
      (node (ref "U4") (pin "4") (pinfunction "SDA_4") (pintype "unspecified"))
    )
    (net (code "25") (name "IO25") (class "Default")
      (node (ref "H2") (pin "9") (pinfunction "9_9") (pintype "unspecified"))
      (node (ref "LED16") (pin "4") (pinfunction "DIN_4") (pintype "unspecified"))
      (node (ref "U1") (pin "10") (pinfunction "IO25_10") (pintype "unspecified"))
    )
    (net (code "26") (name "IO26") (class "Default")
      (node (ref "H2") (pin "10") (pinfunction "10_10") (pintype "unspecified"))
      (node (ref "LED10") (pin "4") (pinfunction "DIN_4") (pintype "unspecified"))
      (node (ref "U1") (pin "11") (pinfunction "IO26_11") (pintype "unspecified"))
    )
    (net (code "27") (name "IO27") (class "Default")
      (node (ref "H2") (pin "11") (pinfunction "11_11") (pintype "unspecified"))
      (node (ref "KEYR3") (pin "1") (pinfunction "1_1") (pintype "unspecified"))
      (node (ref "U1") (pin "12") (pinfunction "IO27_12") (pintype "unspecified"))
    )
    (net (code "28") (name "IO32") (class "Default")
      (node (ref "H2") (pin "7") (pinfunction "7_7") (pintype "unspecified"))
      (node (ref "U1") (pin "8") (pinfunction "IO32_8") (pintype "unspecified"))
    )
    (net (code "29") (name "IO33") (class "Default")
      (node (ref "H2") (pin "8") (pinfunction "8_8") (pintype "unspecified"))
      (node (ref "U1") (pin "9") (pinfunction "IO33_9") (pintype "unspecified"))
    )
    (net (code "30") (name "IO34") (class "Default")
      (node (ref "H2") (pin "5") (pinfunction "5_5") (pintype "unspecified"))
      (node (ref "U1") (pin "6") (pinfunction "IO34_6") (pintype "unspecified"))
    )
    (net (code "31") (name "IO35") (class "Default")
      (node (ref "H2") (pin "6") (pinfunction "6_6") (pintype "unspecified"))
      (node (ref "U1") (pin "7") (pinfunction "IO35_7") (pintype "unspecified"))
    )
    (net (code "32") (name "Net-(C6-Pad2)") (class "Default")
      (node (ref "C6") (pin "2") (pinfunction "2_2") (pintype "unspecified"))
      (node (ref "R6") (pin "2") (pinfunction "2_2") (pintype "input"))
    )
    (net (code "33") (name "Net-(LED1-A)") (class "Default")
      (node (ref "LED1") (pin "1") (pinfunction "A_1") (pintype "unspecified"))
      (node (ref "R1") (pin "1") (pinfunction "1_1") (pintype "input"))
    )
    (net (code "34") (name "Net-(LED2-DIN)") (class "Default")
      (node (ref "LED2") (pin "4") (pinfunction "DIN_4") (pintype "unspecified"))
      (node (ref "LED3") (pin "2") (pinfunction "DOUT_2") (pintype "unspecified"))
    )
    (net (code "35") (name "Net-(LED3-DIN)") (class "Default")
      (node (ref "LED3") (pin "4") (pinfunction "DIN_4") (pintype "unspecified"))
      (node (ref "LED4") (pin "2") (pinfunction "DOUT_2") (pintype "unspecified"))
    )
    (net (code "36") (name "Net-(LED4-DIN)") (class "Default")
      (node (ref "LED4") (pin "4") (pinfunction "DIN_4") (pintype "unspecified"))
      (node (ref "LED5") (pin "2") (pinfunction "DOUT_2") (pintype "unspecified"))
    )
    (net (code "37") (name "Net-(LED6-DIN)") (class "Default")
      (node (ref "LED6") (pin "4") (pinfunction "DIN_4") (pintype "unspecified"))
      (node (ref "LED7") (pin "2") (pinfunction "DOUT_2") (pintype "unspecified"))
    )
    (net (code "38") (name "Net-(LED7-DIN)") (class "Default")
      (node (ref "LED7") (pin "4") (pinfunction "DIN_4") (pintype "unspecified"))
      (node (ref "LED8") (pin "2") (pinfunction "DOUT_2") (pintype "unspecified"))
    )
    (net (code "39") (name "Net-(LED8-DIN)") (class "Default")
      (node (ref "LED8") (pin "4") (pinfunction "DIN_4") (pintype "unspecified"))
      (node (ref "LED9") (pin "2") (pinfunction "DOUT_2") (pintype "unspecified"))
    )
    (net (code "40") (name "Net-(LED10-DOUT)") (class "Default")
      (node (ref "LED10") (pin "2") (pinfunction "DOUT_2") (pintype "unspecified"))
      (node (ref "LED9") (pin "4") (pinfunction "DIN_4") (pintype "unspecified"))
    )
    (net (code "41") (name "Net-(LED12-DIN)") (class "Default")
      (node (ref "LED12") (pin "4") (pinfunction "DIN_4") (pintype "unspecified"))
      (node (ref "LED13") (pin "2") (pinfunction "DOUT_2") (pintype "unspecified"))
    )
    (net (code "42") (name "Net-(LED13-DIN)") (class "Default")
      (node (ref "LED13") (pin "4") (pinfunction "DIN_4") (pintype "unspecified"))
      (node (ref "LED14") (pin "2") (pinfunction "DOUT_2") (pintype "unspecified"))
    )
    (net (code "43") (name "Net-(LED14-DIN)") (class "Default")
      (node (ref "LED14") (pin "4") (pinfunction "DIN_4") (pintype "unspecified"))
      (node (ref "LED15") (pin "2") (pinfunction "DOUT_2") (pintype "unspecified"))
    )
    (net (code "44") (name "Net-(LED15-DIN)") (class "Default")
      (node (ref "LED15") (pin "4") (pinfunction "DIN_4") (pintype "unspecified"))
      (node (ref "LED16") (pin "2") (pinfunction "DOUT_2") (pintype "unspecified"))
    )
    (net (code "45") (name "Net-(Q3-B)") (class "Default")
      (node (ref "Q3") (pin "1") (pinfunction "B_1") (pintype "unspecified"))
      (node (ref "R4") (pin "1") (pinfunction "1_1") (pintype "input"))
    )
    (net (code "46") (name "Net-(Q4-B)") (class "Default")
      (node (ref "Q4") (pin "1") (pinfunction "B_1") (pintype "unspecified"))
      (node (ref "R5") (pin "1") (pinfunction "1_1") (pintype "input"))
    )
    (net (code "47") (name "Net-(U2-V3)") (class "Default")
      (node (ref "C7") (pin "2") (pinfunction "2_2") (pintype "unspecified"))
      (node (ref "U2") (pin "10") (pinfunction "V3_10") (pintype "unspecified"))
    )
    (net (code "48") (name "RTS") (class "Default")
      (node (ref "Q3") (pin "2") (pinfunction "E_2") (pintype "unspecified"))
      (node (ref "R5") (pin "2") (pinfunction "2_2") (pintype "input"))
      (node (ref "U2") (pin "6") (pinfunction "RTS#_6") (pintype "unspecified"))
    )
    (net (code "49") (name "SD0") (class "Default")
      (node (ref "H3") (pin "9") (pinfunction "9_9") (pintype "unspecified"))
    )
    (net (code "50") (name "SD1") (class "Default")
      (node (ref "H3") (pin "10") (pinfunction "10_10") (pintype "unspecified"))
    )
    (net (code "51") (name "SD2") (class "Default")
      (node (ref "H2") (pin "17") (pinfunction "17_17") (pintype "unspecified"))
      (node (ref "U1") (pin "17") (pinfunction "SD2_17") (pintype "unspecified"))
    )
    (net (code "52") (name "SD3") (class "Default")
      (node (ref "H2") (pin "16") (pinfunction "16_16") (pintype "unspecified"))
      (node (ref "U1") (pin "18") (pinfunction "SD3_18") (pintype "unspecified"))
    )
    (net (code "53") (name "S_VN") (class "Default")
      (node (ref "H2") (pin "4") (pinfunction "4_4") (pintype "unspecified"))
      (node (ref "U1") (pin "5") (pinfunction "SENSOR_VN_5") (pintype "unspecified"))
    )
    (net (code "54") (name "S_VP") (class "Default")
      (node (ref "H2") (pin "3") (pinfunction "3_3") (pintype "unspecified"))
      (node (ref "U1") (pin "4") (pinfunction "SENSOR_VP_4") (pintype "unspecified"))
    )
    (net (code "55") (name "U0RXD") (class "Default")
      (node (ref "H3") (pin "14") (pinfunction "14_14") (pintype "unspecified"))
      (node (ref "U2") (pin "8") (pinfunction "TXD_8") (pintype "unspecified"))
    )
    (net (code "56") (name "U0TXD") (class "Default")
      (node (ref "H3") (pin "13") (pinfunction "13_13") (pintype "unspecified"))
      (node (ref "U2") (pin "9") (pinfunction "RXD_9") (pintype "unspecified"))
    )
    (net (code "57") (name "VCC") (class "Default")
      (node (ref "C1") (pin "2") (pinfunction "2_2") (pintype "input"))
      (node (ref "C2") (pin "2") (pinfunction "2_2") (pintype "unspecified"))
      (node (ref "F1") (pin "2") (pinfunction "2_2") (pintype "unspecified"))
      (node (ref "H2") (pin "19") (pinfunction "19_19") (pintype "unspecified"))
      (node (ref "LED10") (pin "1") (pinfunction "VDD_1") (pintype "unspecified"))
      (node (ref "LED11") (pin "1") (pinfunction "VDD_1") (pintype "unspecified"))
      (node (ref "LED12") (pin "1") (pinfunction "VDD_1") (pintype "unspecified"))
      (node (ref "LED13") (pin "1") (pinfunction "VDD_1") (pintype "unspecified"))
      (node (ref "LED14") (pin "1") (pinfunction "VDD_1") (pintype "unspecified"))
      (node (ref "LED15") (pin "1") (pinfunction "VDD_1") (pintype "unspecified"))
      (node (ref "LED16") (pin "1") (pinfunction "VDD_1") (pintype "unspecified"))
      (node (ref "LED2") (pin "1") (pinfunction "VDD_1") (pintype "unspecified"))
      (node (ref "LED3") (pin "1") (pinfunction "VDD_1") (pintype "unspecified"))
      (node (ref "LED4") (pin "1") (pinfunction "VDD_1") (pintype "unspecified"))
      (node (ref "LED5") (pin "1") (pinfunction "VDD_1") (pintype "unspecified"))
      (node (ref "LED6") (pin "1") (pinfunction "VDD_1") (pintype "unspecified"))
      (node (ref "LED7") (pin "1") (pinfunction "VDD_1") (pintype "unspecified"))
      (node (ref "LED8") (pin "1") (pinfunction "VDD_1") (pintype "unspecified"))
      (node (ref "LED9") (pin "1") (pinfunction "VDD_1") (pintype "unspecified"))
      (node (ref "U2") (pin "7") (pinfunction "VCC_7") (pintype "unspecified"))
      (node (ref "U3") (pin "3") (pinfunction "VIN_3") (pintype "unspecified"))
    )
    (net (code "58") (name "unconnected-(LED2-DOUT-Pad2)") (class "Default")
      (node (ref "LED2") (pin "2") (pinfunction "DOUT_2") (pintype "unspecified"))
    )
    (net (code "59") (name "unconnected-(LED6-DOUT-Pad2)") (class "Default")
      (node (ref "LED6") (pin "2") (pinfunction "DOUT_2") (pintype "unspecified+no_connect"))
    )
    (net (code "60") (name "unconnected-(LED11-DIN-Pad4)") (class "Default")
      (node (ref "LED11") (pin "4") (pinfunction "DIN_4") (pintype "unspecified"))
    )
    (net (code "61") (name "unconnected-(LED11-DOUT-Pad2)") (class "Default")
      (node (ref "LED11") (pin "2") (pinfunction "DOUT_2") (pintype "unspecified+no_connect"))
    )
    (net (code "62") (name "unconnected-(LED12-DOUT-Pad2)") (class "Default")
      (node (ref "LED12") (pin "2") (pinfunction "DOUT_2") (pintype "unspecified+no_connect"))
    )
    (net (code "63") (name "unconnected-(U1-GND-Pad1)") (class "Default")
      (node (ref "U1") (pin "1") (pinfunction "GND_1") (pintype "unspecified"))
    )
    (net (code "64") (name "unconnected-(U1-GND-Pad38)") (class "Default")
      (node (ref "U1") (pin "38") (pinfunction "GND_38") (pintype "unspecified"))
    )
    (net (code "65") (name "unconnected-(U1-IO0-Pad25)") (class "Default")
      (node (ref "U1") (pin "25") (pinfunction "IO0_25") (pintype "unspecified"))
    )
    (net (code "66") (name "unconnected-(U1-IO2-Pad24)") (class "Default")
      (node (ref "U1") (pin "24") (pinfunction "IO2_24") (pintype "unspecified"))
    )
    (net (code "67") (name "unconnected-(U1-IO4-Pad26)") (class "Default")
      (node (ref "U1") (pin "26") (pinfunction "IO4_26") (pintype "unspecified"))
    )
    (net (code "68") (name "unconnected-(U1-IO5-Pad29)") (class "Default")
      (node (ref "U1") (pin "29") (pinfunction "IO5_29") (pintype "unspecified"))
    )
    (net (code "69") (name "unconnected-(U1-IO15-Pad23)") (class "Default")
      (node (ref "U1") (pin "23") (pinfunction "IO15_23") (pintype "unspecified"))
    )
    (net (code "70") (name "unconnected-(U1-IO16-Pad27)") (class "Default")
      (node (ref "U1") (pin "27") (pinfunction "IO16_27") (pintype "unspecified"))
    )
    (net (code "71") (name "unconnected-(U1-IO17-Pad28)") (class "Default")
      (node (ref "U1") (pin "28") (pinfunction "IO17_28") (pintype "unspecified"))
    )
    (net (code "72") (name "unconnected-(U1-IO18-Pad30)") (class "Default")
      (node (ref "U1") (pin "30") (pinfunction "IO18_30") (pintype "unspecified"))
    )
    (net (code "73") (name "unconnected-(U1-IO19-Pad31)") (class "Default")
      (node (ref "U1") (pin "31") (pinfunction "IO19_31") (pintype "unspecified"))
    )
    (net (code "74") (name "unconnected-(U1-IO21-Pad33)") (class "Default")
      (node (ref "U1") (pin "33") (pinfunction "IO21_33") (pintype "unspecified"))
    )
    (net (code "75") (name "unconnected-(U1-IO22-Pad36)") (class "Default")
      (node (ref "U1") (pin "36") (pinfunction "IO22_36") (pintype "unspecified"))
    )
    (net (code "76") (name "unconnected-(U1-IO23-Pad37)") (class "Default")
      (node (ref "U1") (pin "37") (pinfunction "IO23_37") (pintype "unspecified"))
    )
    (net (code "77") (name "unconnected-(U1-NC-Pad32)") (class "Default")
      (node (ref "U1") (pin "32") (pinfunction "NC_32") (pintype "unspecified+no_connect"))
    )
    (net (code "78") (name "unconnected-(U1-RXD0-Pad34)") (class "Default")
      (node (ref "U1") (pin "34") (pinfunction "RXD0_34") (pintype "unspecified"))
    )
    (net (code "79") (name "unconnected-(U1-SD0-Pad21)") (class "Default")
      (node (ref "U1") (pin "21") (pinfunction "SD0_21") (pintype "unspecified"))
    )
    (net (code "80") (name "unconnected-(U1-SD1-Pad22)") (class "Default")
      (node (ref "U1") (pin "22") (pinfunction "SD1_22") (pintype "unspecified"))
    )
    (net (code "81") (name "unconnected-(U1-TXD0-Pad35)") (class "Default")
      (node (ref "U1") (pin "35") (pinfunction "TXD0_35") (pintype "unspecified"))
    )
    (net (code "82") (name "unconnected-(U2-CTS#-Pad5)") (class "Default")
      (node (ref "U2") (pin "5") (pinfunction "CTS#_5") (pintype "unspecified+no_connect"))
    )
    (net (code "83") (name "unconnected-(U2-UD--Pad2)") (class "Default")
      (node (ref "U2") (pin "2") (pinfunction "UD-_2") (pintype "unspecified"))
    )
    (net (code "84") (name "unconnected-(U4-NC-Pad2)") (class "Default")
      (node (ref "U4") (pin "2") (pinfunction "NC_2") (pintype "unspecified+no_connect"))
    )
    (net (code "85") (name "unconnected-(U4-NC-Pad5)") (class "Default")
      (node (ref "U4") (pin "5") (pinfunction "NC_5") (pintype "unspecified+no_connect"))
    )
    (net (code "86") (name "unconnected-(USB1-ID-Pad4)") (class "Default")
      (node (ref "USB1") (pin "4") (pinfunction "ID_4") (pintype "unspecified+no_connect"))
    )
  )
)
